# radio_module_V4_0.net
KiCad netlist of a schematic drawn in EAGLE
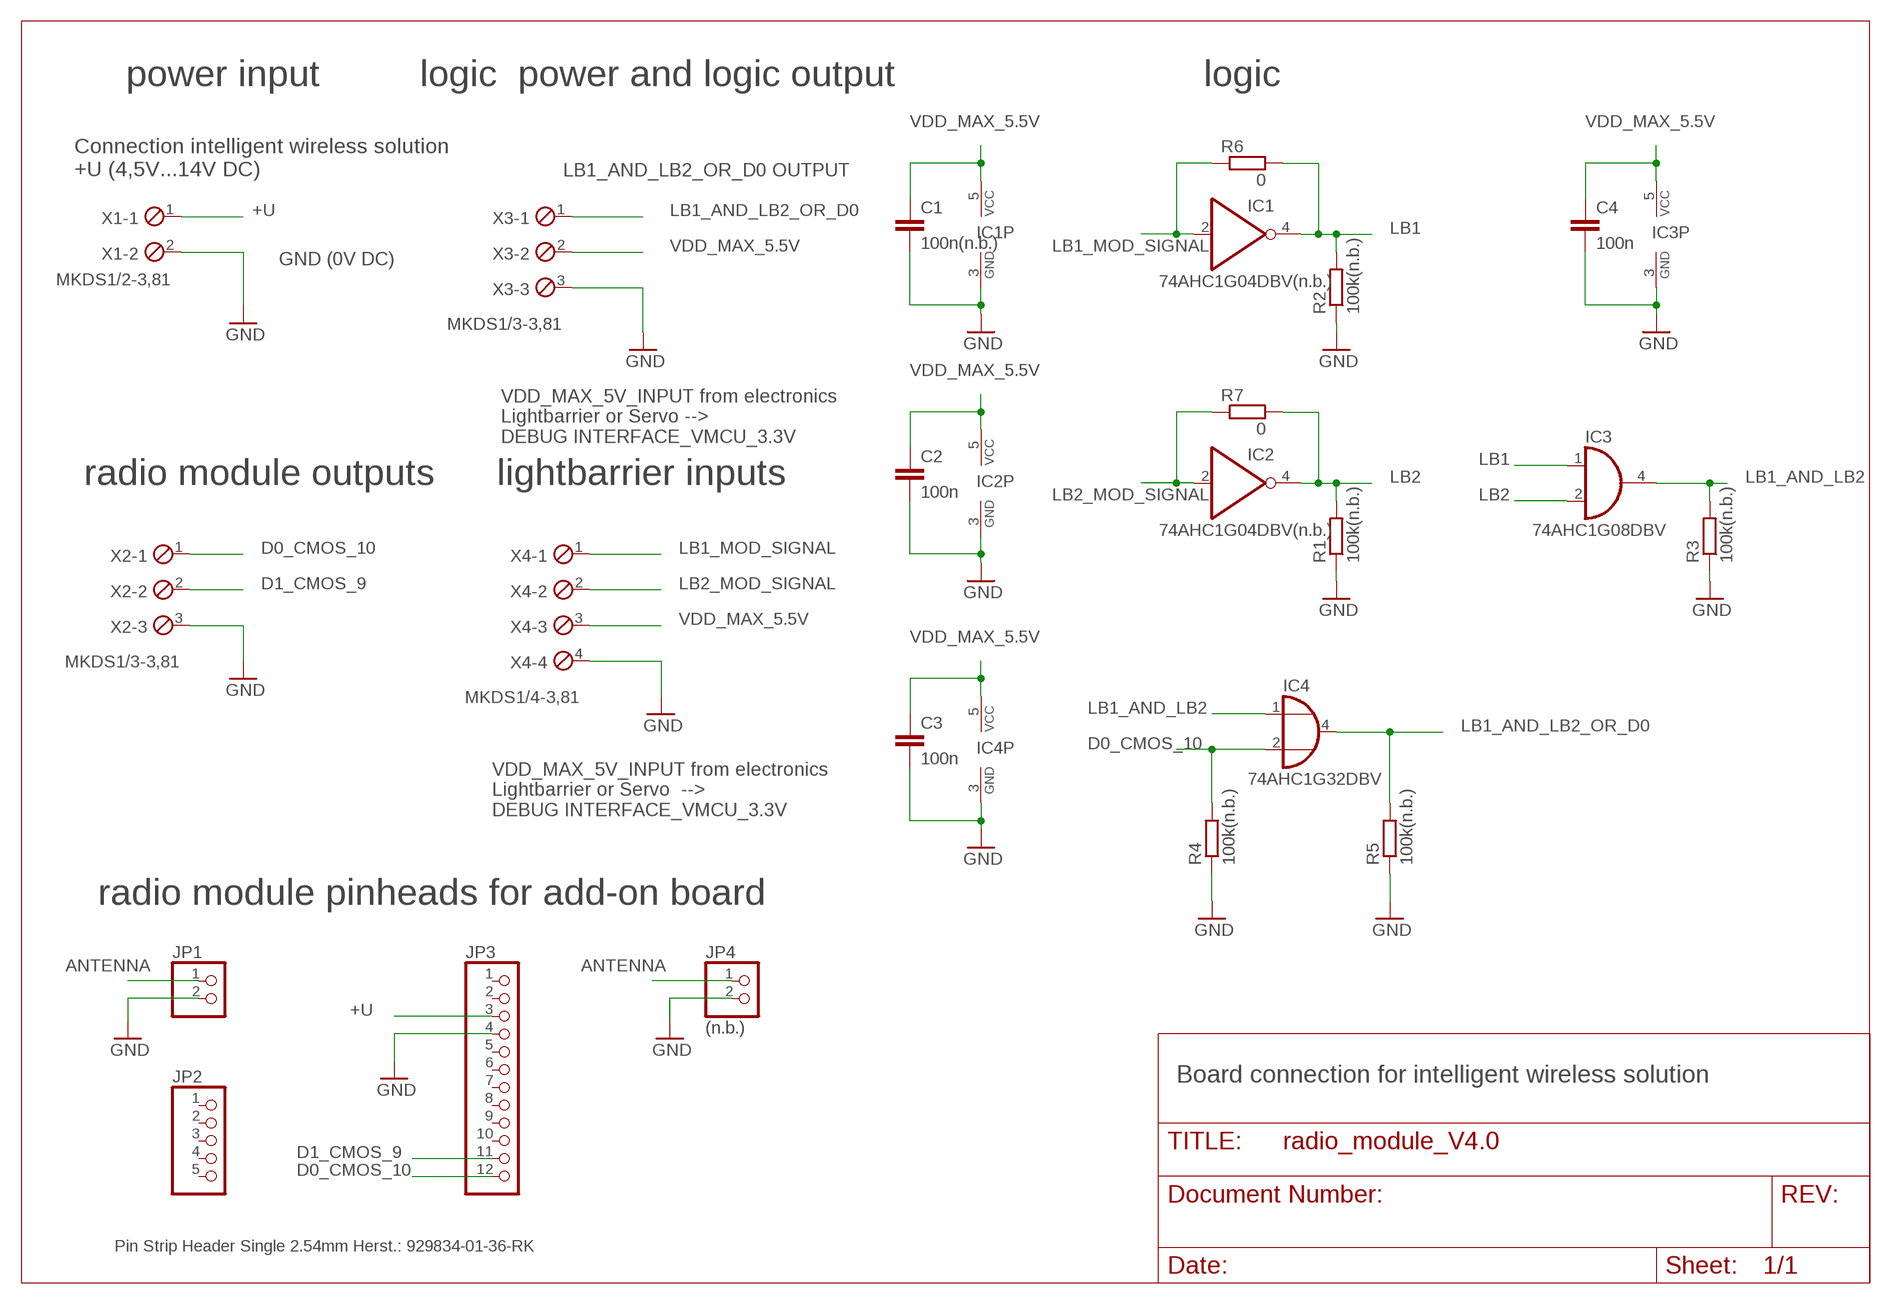
[diagram p0: schematic, sheet 1]

(export (version "E")
  (design (tool "Eeschema 10.0.6"))
  (components
    (comp (ref "C1")
      (value "100n(n.b.)")
      (footprint "eagle-import:C0805")
      (libsource (lib "eagle-import") (part "C-EUC0805"))
    )
    (comp (ref "C2")
      (value "100n")
      (footprint "eagle-import:C0805")
      (libsource (lib "eagle-import") (part "C-EUC0805"))
    )
    (comp (ref "C3")
      (value "100n")
      (footprint "eagle-import:C0805")
      (libsource (lib "eagle-import") (part "C-EUC0805"))
    )
    (comp (ref "C4")
      (value "100n")
      (footprint "eagle-import:C0805")
      (libsource (lib "eagle-import") (part "C-EUC0805"))
    )
    (comp (ref "IC1")
      (value "74AHC1G04DBV(n.b.)")
      (footprint "eagle-import:SOT23-5")
      (libsource (lib "eagle-import") (part "741G04DBVAHC"))
    )
    (comp (ref "IC2")
      (value "74AHC1G04DBV(n.b.)")
      (footprint "eagle-import:SOT23-5")
      (libsource (lib "eagle-import") (part "741G04DBVAHC"))
    )
    (comp (ref "IC3")
      (value "74AHC1G08DBV")
      (footprint "eagle-import:SOT23-5")
      (libsource (lib "eagle-import") (part "741G08DBVAHC"))
    )
    (comp (ref "IC4")
      (value "74AHC1G32DBV")
      (footprint "eagle-import:SOT23-5")
      (libsource (lib "eagle-import") (part "741G32DBVAHC"))
    )
    (comp (ref "JP1")
      (value "PINHD-1X2")
      (footprint "eagle-import:1X02")
      (libsource (lib "eagle-import") (part "PINHD-1X2"))
    )
    (comp (ref "JP2")
      (value "PINHD-1X5")
      (footprint "eagle-import:1X05")
      (libsource (lib "eagle-import") (part "PINHD-1X5"))
    )
    (comp (ref "JP3")
      (value "PINHD-1X12")
      (footprint "eagle-import:1X12")
      (libsource (lib "eagle-import") (part "PINHD-1X12"))
    )
    (comp (ref "JP4")
      (value "(n.b.)")
      (footprint "eagle-import:1X02")
      (libsource (lib "eagle-import") (part "PINHD-1X2"))
    )
    (comp (ref "R1")
      (value "100k(n.b.)")
      (footprint "eagle-import:R0805")
      (libsource (lib "eagle-import") (part "resistor_R-EU_R0805"))
    )
    (comp (ref "R2")
      (value "100k(n.b.)")
      (footprint "eagle-import:R0805")
      (libsource (lib "eagle-import") (part "resistor_R-EU_R0805"))
    )
    (comp (ref "R3")
      (value "100k(n.b.)")
      (footprint "eagle-import:R0805")
      (libsource (lib "eagle-import") (part "resistor_R-EU_R0805"))
    )
    (comp (ref "R4")
      (value "100k(n.b.)")
      (footprint "eagle-import:R0805")
      (libsource (lib "eagle-import") (part "resistor_R-EU_R0805"))
    )
    (comp (ref "R5")
      (value "100k(n.b.)")
      (footprint "eagle-import:R0805")
      (libsource (lib "eagle-import") (part "resistor_R-EU_R0805"))
    )
    (comp (ref "R6")
      (value "0")
      (footprint "eagle-import:R0805")
      (libsource (lib "eagle-import") (part "R-EU_R0805"))
    )
    (comp (ref "R7")
      (value "0")
      (footprint "eagle-import:R0805")
      (libsource (lib "eagle-import") (part "R-EU_R0805"))
    )
    (comp (ref "X1")
      (value "MKDS1/2-3,81")
      (footprint "eagle-import:2POL381")
      (libsource (lib "eagle-import") (part "MKDS1/2-3,81"))
    )
    (comp (ref "X2")
      (value "MKDS1/3-3,81")
      (footprint "eagle-import:3POL381")
      (libsource (lib "eagle-import") (part "MKDS1/3-3,81"))
    )
    (comp (ref "X3")
      (value "MKDS1/3-3,81")
      (footprint "eagle-import:3POL381")
      (libsource (lib "eagle-import") (part "MKDS1/3-3,81"))
    )
    (comp (ref "X4")
      (value "MKDS1/4-3,81")
      (footprint "eagle-import:4POL381")
      (libsource (lib "eagle-import") (part "MKDS1/4-3,81"))
    )
  )
  (nets
    (net (code "1") (name "/+U") (class "Default")
      (node (ref "JP3") (pin "3") (pinfunction "3_3") (pintype "passive"))
      (node (ref "X1") (pin "1") (pinfunction "1_1") (pintype "passive"))
    )
    (net (code "2") (name "/ANTENNA") (class "Default")
      (node (ref "JP1") (pin "1") (pinfunction "1_1") (pintype "passive"))
      (node (ref "JP4") (pin "1") (pinfunction "1_1") (pintype "passive"))
    )
    (net (code "3") (name "/D0_CMOS_10") (class "Default")
      (node (ref "IC4") (pin "2") (pinfunction "I1_2") (pintype "input"))
      (node (ref "JP3") (pin "12") (pinfunction "12_12") (pintype "passive"))
      (node (ref "R4") (pin "2") (pinfunction "2_2") (pintype "passive"))
      (node (ref "X2") (pin "1") (pinfunction "1_1") (pintype "passive"))
    )
    (net (code "4") (name "/D1_CMOS_9") (class "Default")
      (node (ref "JP3") (pin "11") (pinfunction "11_11") (pintype "passive"))
      (node (ref "X2") (pin "2") (pinfunction "1_2") (pintype "passive"))
    )
    (net (code "5") (name "/LB1") (class "Default")
      (node (ref "IC1") (pin "4") (pinfunction "O_4") (pintype "output"))
      (node (ref "IC3") (pin "1") (pinfunction "I0_1") (pintype "input"))
      (node (ref "R2") (pin "2") (pinfunction "2_2") (pintype "passive"))
      (node (ref "R6") (pin "2") (pinfunction "2_2") (pintype "passive"))
    )
    (net (code "6") (name "/LB1_AND_LB2") (class "Default")
      (node (ref "IC3") (pin "4") (pinfunction "O_4") (pintype "output"))
      (node (ref "IC4") (pin "1") (pinfunction "I0_1") (pintype "input"))
      (node (ref "R3") (pin "2") (pinfunction "2_2") (pintype "passive"))
    )
    (net (code "7") (name "/LB1_AND_LB2_OR_D0") (class "Default")
      (node (ref "IC4") (pin "4") (pinfunction "O_4") (pintype "output"))
      (node (ref "R5") (pin "2") (pinfunction "2_2") (pintype "passive"))
      (node (ref "X3") (pin "1") (pinfunction "1_1") (pintype "passive"))
    )
    (net (code "8") (name "/LB1_MOD_SIGNAL") (class "Default")
      (node (ref "IC1") (pin "2") (pinfunction "I_2") (pintype "input"))
      (node (ref "R6") (pin "1") (pinfunction "1_1") (pintype "passive"))
      (node (ref "X4") (pin "1") (pinfunction "1_1") (pintype "passive"))
    )
    (net (code "9") (name "/LB2") (class "Default")
      (node (ref "IC2") (pin "4") (pinfunction "O_4") (pintype "output"))
      (node (ref "IC3") (pin "2") (pinfunction "I1_2") (pintype "input"))
      (node (ref "R1") (pin "2") (pinfunction "2_2") (pintype "passive"))
      (node (ref "R7") (pin "2") (pinfunction "2_2") (pintype "passive"))
    )
    (net (code "10") (name "/LB2_MOD_SIGNAL") (class "Default")
      (node (ref "IC2") (pin "2") (pinfunction "I_2") (pintype "input"))
      (node (ref "R7") (pin "1") (pinfunction "1_1") (pintype "passive"))
      (node (ref "X4") (pin "2") (pinfunction "1_2") (pintype "passive"))
    )
    (net (code "11") (name "/VDD_MAX_5.5V") (class "Default")
      (node (ref "C1") (pin "1") (pinfunction "1_1") (pintype "passive"))
      (node (ref "C2") (pin "1") (pinfunction "1_1") (pintype "passive"))
      (node (ref "C3") (pin "1") (pinfunction "1_1") (pintype "passive"))
      (node (ref "C4") (pin "1") (pinfunction "1_1") (pintype "passive"))
      (node (ref "IC1") (pin "5") (pinfunction "VCC_5") (pintype "power_in"))
      (node (ref "IC2") (pin "5") (pinfunction "VCC_5") (pintype "power_in"))
      (node (ref "IC3") (pin "5") (pinfunction "VCC_5") (pintype "power_in"))
      (node (ref "IC4") (pin "5") (pinfunction "VCC_5") (pintype "power_in"))
      (node (ref "X3") (pin "2") (pinfunction "1_2") (pintype "passive"))
      (node (ref "X4") (pin "3") (pinfunction "1_3") (pintype "passive"))
    )
    (net (code "12") (name "GND") (class "Default")
      (node (ref "C1") (pin "2") (pinfunction "2_2") (pintype "passive"))
      (node (ref "C2") (pin "2") (pinfunction "2_2") (pintype "passive"))
      (node (ref "C3") (pin "2") (pinfunction "2_2") (pintype "passive"))
      (node (ref "C4") (pin "2") (pinfunction "2_2") (pintype "passive"))
      (node (ref "IC1") (pin "3") (pinfunction "GND_3") (pintype "power_in"))
      (node (ref "IC2") (pin "3") (pinfunction "GND_3") (pintype "power_in"))
      (node (ref "IC3") (pin "3") (pinfunction "GND_3") (pintype "power_in"))
      (node (ref "IC4") (pin "3") (pinfunction "GND_3") (pintype "power_in"))
      (node (ref "JP1") (pin "2") (pinfunction "2_2") (pintype "passive"))
      (node (ref "JP3") (pin "4") (pinfunction "4_4") (pintype "passive"))
      (node (ref "JP4") (pin "2") (pinfunction "2_2") (pintype "passive"))
      (node (ref "R1") (pin "1") (pinfunction "1_1") (pintype "passive"))
      (node (ref "R2") (pin "1") (pinfunction "1_1") (pintype "passive"))
      (node (ref "R3") (pin "1") (pinfunction "1_1") (pintype "passive"))
      (node (ref "R4") (pin "1") (pinfunction "1_1") (pintype "passive"))
      (node (ref "R5") (pin "1") (pinfunction "1_1") (pintype "passive"))
      (node (ref "X1") (pin "2") (pinfunction "1_2") (pintype "passive"))
      (node (ref "X2") (pin "3") (pinfunction "1_3") (pintype "passive"))
      (node (ref "X3") (pin "3") (pinfunction "1_3") (pintype "passive"))
      (node (ref "X4") (pin "4") (pinfunction "1_4") (pintype "passive"))
    )
    (net (code "13") (name "unconnected-(JP2-Pad1)") (class "Default")
      (node (ref "JP2") (pin "1") (pinfunction "1_1") (pintype "passive"))
    )
    (net (code "14") (name "unconnected-(JP2-Pad2)") (class "Default")
      (node (ref "JP2") (pin "2") (pinfunction "2_2") (pintype "passive"))
    )
    (net (code "15") (name "unconnected-(JP2-Pad3)") (class "Default")
      (node (ref "JP2") (pin "3") (pinfunction "3_3") (pintype "passive"))
    )
    (net (code "16") (name "unconnected-(JP2-Pad4)") (class "Default")
      (node (ref "JP2") (pin "4") (pinfunction "4_4") (pintype "passive"))
    )
    (net (code "17") (name "unconnected-(JP2-Pad5)") (class "Default")
      (node (ref "JP2") (pin "5") (pinfunction "5_5") (pintype "passive"))
    )
    (net (code "18") (name "unconnected-(JP3-Pad1)") (class "Default")
      (node (ref "JP3") (pin "1") (pinfunction "1_1") (pintype "passive"))
    )
    (net (code "19") (name "unconnected-(JP3-Pad2)") (class "Default")
      (node (ref "JP3") (pin "2") (pinfunction "2_2") (pintype "passive"))
    )
    (net (code "20") (name "unconnected-(JP3-Pad5)") (class "Default")
      (node (ref "JP3") (pin "5") (pinfunction "5_5") (pintype "passive"))
    )
    (net (code "21") (name "unconnected-(JP3-Pad6)") (class "Default")
      (node (ref "JP3") (pin "6") (pinfunction "6_6") (pintype "passive"))
    )
    (net (code "22") (name "unconnected-(JP3-Pad7)") (class "Default")
      (node (ref "JP3") (pin "7") (pinfunction "7_7") (pintype "passive"))
    )
    (net (code "23") (name "unconnected-(JP3-Pad8)") (class "Default")
      (node (ref "JP3") (pin "8") (pinfunction "8_8") (pintype "passive"))
    )
    (net (code "24") (name "unconnected-(JP3-Pad9)") (class "Default")
      (node (ref "JP3") (pin "9") (pinfunction "9_9") (pintype "passive"))
    )
    (net (code "25") (name "unconnected-(JP3-Pad10)") (class "Default")
      (node (ref "JP3") (pin "10") (pinfunction "10_10") (pintype "passive"))
    )
  )
)
